# 11_-_AUDIO1.net
KiCad netlist of a schematic drawn in Altium Designer
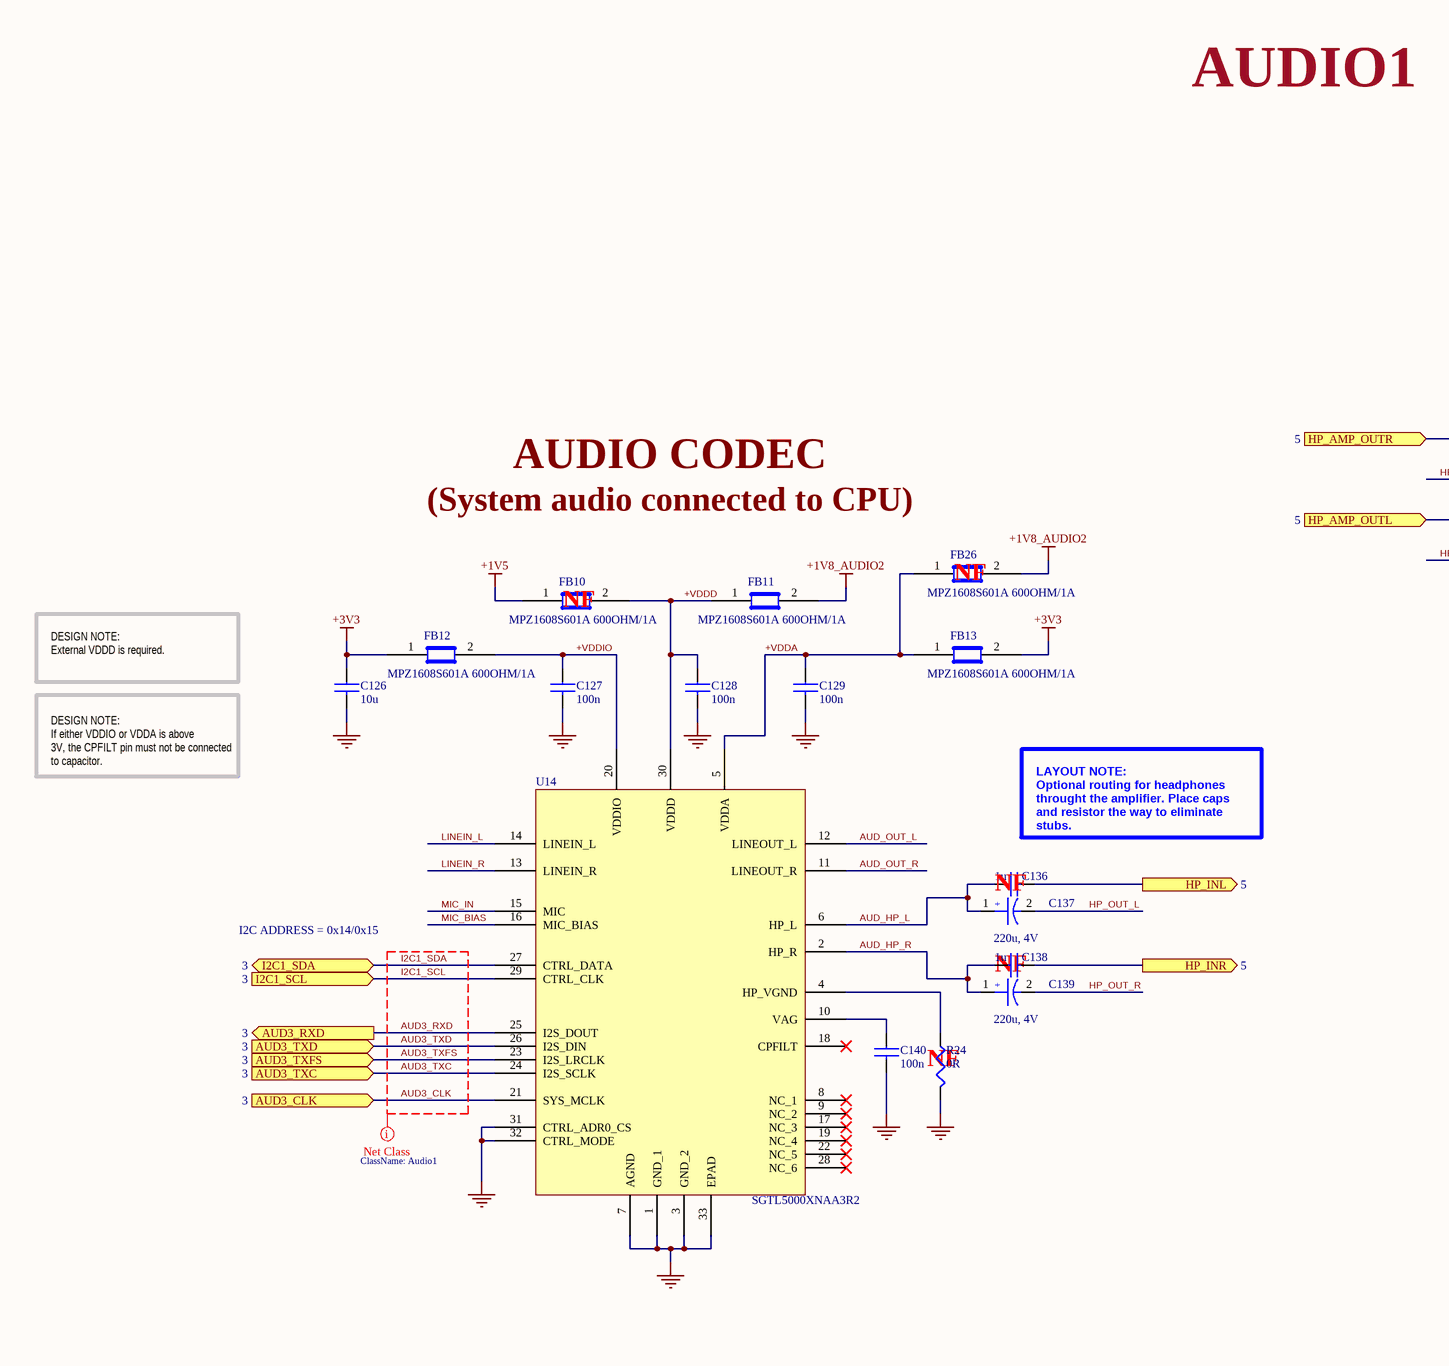
[diagram p0: [11] - AUDIO1.SchDoc, left]
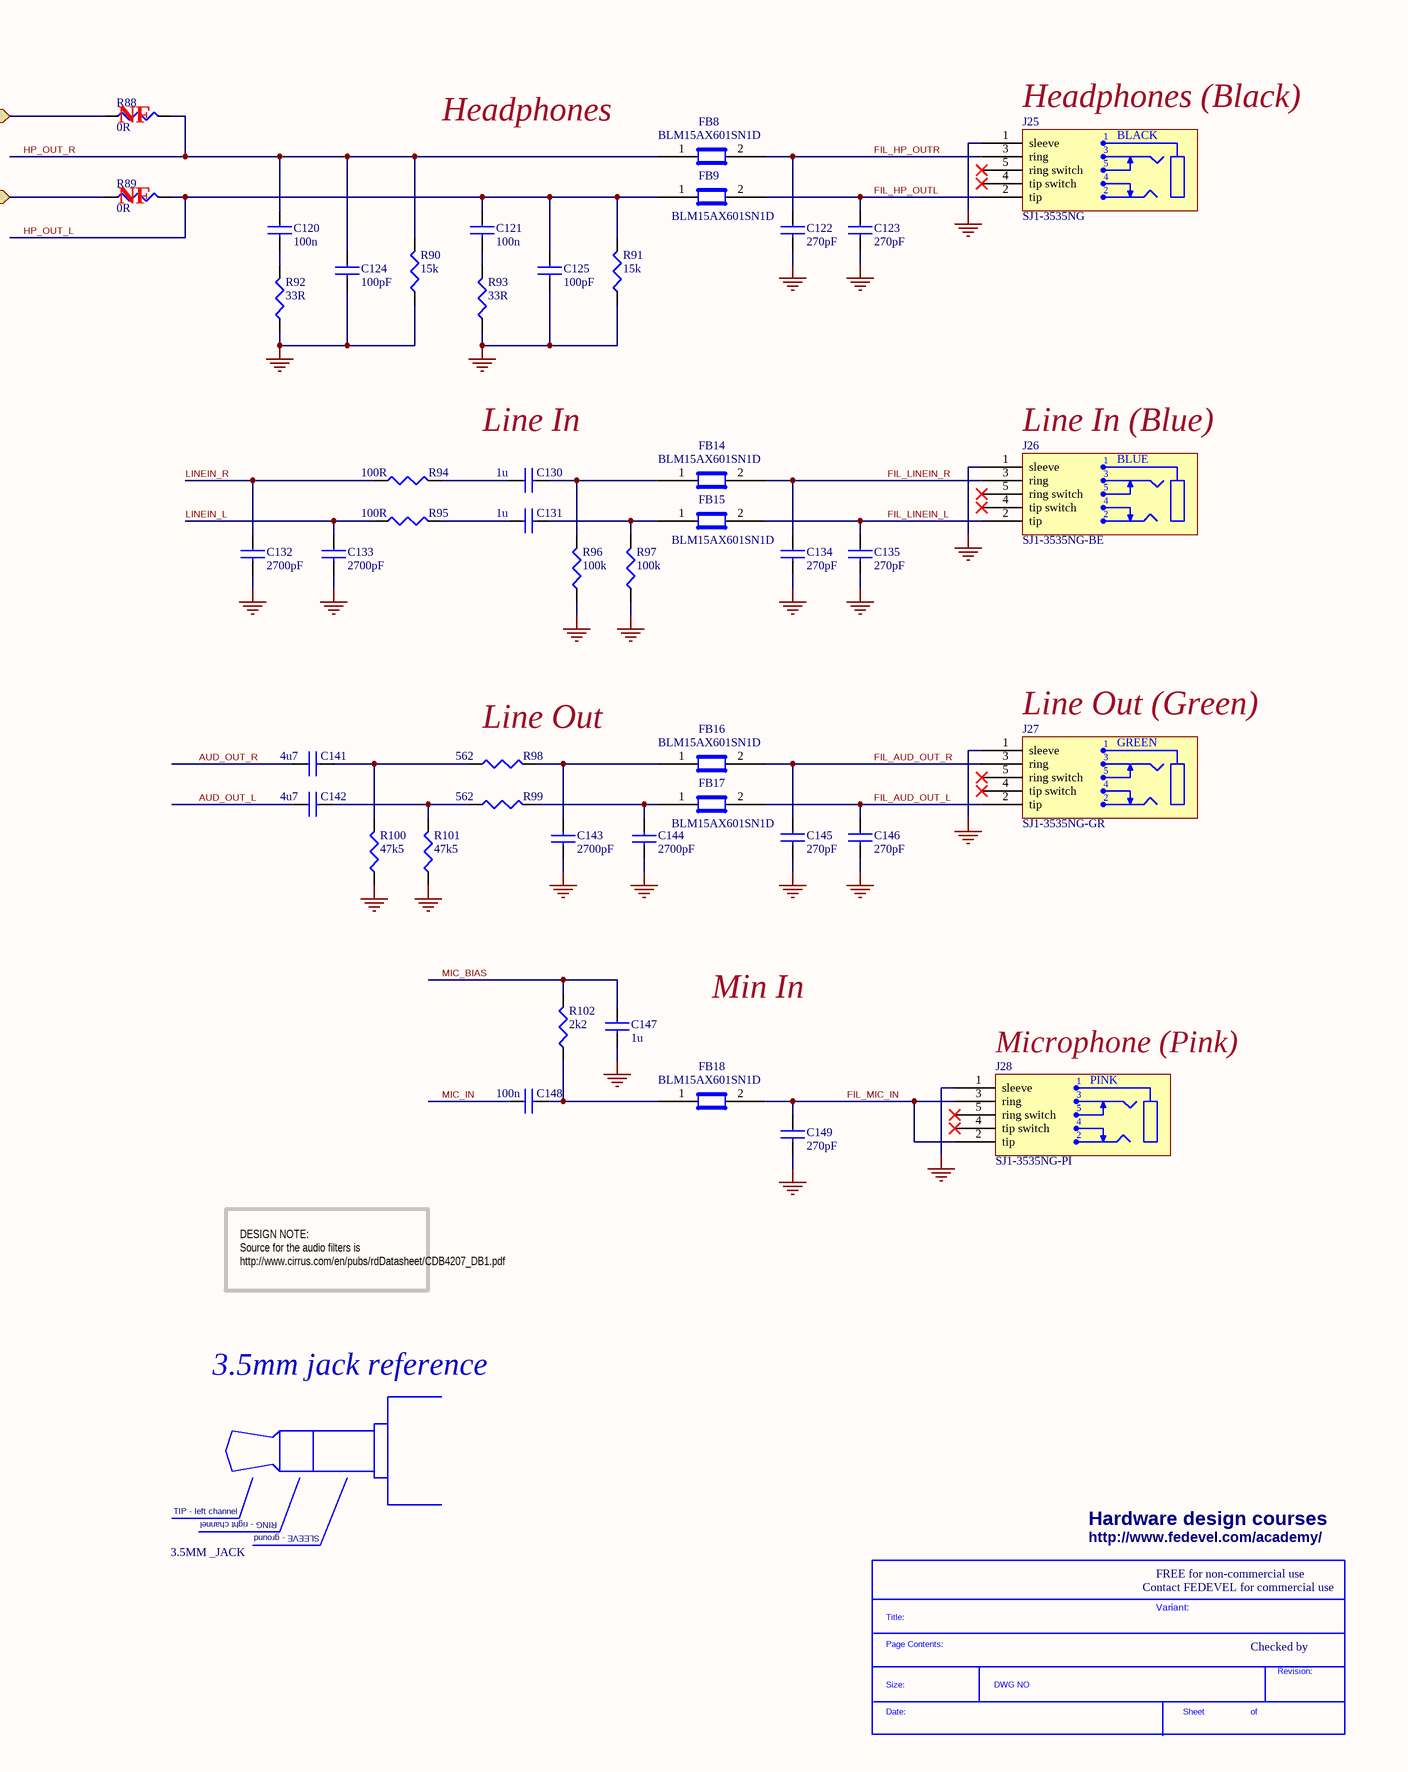
[diagram p1: [11] - AUDIO1.SchDoc, right]

(export (version "E")
  (design (tool "Eeschema 10.0.6"))
  (components
    (comp (ref "C120")
      (value "100n")
      (footprint "C0402")
      (description "CAP CER .10UF 50V X5R 10% 0402")
      (fields
        (field (name "MANUFACTURER") "TDK Corporation")
        (field (name "MANUFACTURER PART NUMBER") "C1005X5R1H104K")
      )
      (libsource (lib "Integrated_Library_RF_FEB_2012") (part "C1005X5R1H104K"))
    )
    (comp (ref "C121")
      (value "100n")
      (footprint "C0402")
      (description "CAP CER .10UF 50V X5R 10% 0402")
      (fields
        (field (name "MANUFACTURER") "TDK Corporation")
        (field (name "MANUFACTURER PART NUMBER") "C1005X5R1H104K")
      )
      (libsource (lib "Integrated_Library_RF_FEB_2012") (part "C1005X5R1H104K"))
    )
    (comp (ref "C122")
      (value "270pF")
      (footprint "C0402")
      (description "CAP CER 270PF 50V 10% X7R 0402")
      (fields
        (field (name "MANUFACTURER") "Murata Electronics North America")
        (field (name "MANUFACTURER PART NUMBER") "GRM155R71H271KA01D")
        (field (name ".CHECKED PCB") "RF")
        (field (name ".CHECKED SCH") "RF")
      )
      (libsource (lib "Integrated_Library_RF_FEB_2012") (part "GRM155R71H271KA01D"))
    )
    (comp (ref "C123")
      (value "270pF")
      (footprint "C0402")
      (description "CAP CER 270PF 50V 10% X7R 0402")
      (fields
        (field (name "MANUFACTURER") "Murata Electronics North America")
        (field (name "MANUFACTURER PART NUMBER") "GRM155R71H271KA01D")
        (field (name ".CHECKED PCB") "RF")
        (field (name ".CHECKED SCH") "RF")
      )
      (libsource (lib "Integrated_Library_RF_FEB_2012") (part "GRM155R71H271KA01D"))
    )
    (comp (ref "C124")
      (value "100pF")
      (footprint "C0402")
      (description "CAP CER 100PF 50V 5% NP0 0402")
      (fields
        (field (name "MANUFACTURER") "TDK Corporation")
        (field (name "MANUFACTURER PART NUMBER") "C1005C0G1H101J")
        (field (name ".CHECKED PCB") "RF")
        (field (name ".CHECKED SCH") "RF")
      )
      (libsource (lib "Integrated_Library_RF_FEB_2012") (part "C1005C0G1H101J"))
    )
    (comp (ref "C125")
      (value "100pF")
      (footprint "C0402")
      (description "CAP CER 100PF 50V 5% NP0 0402")
      (fields
        (field (name "MANUFACTURER") "TDK Corporation")
        (field (name "MANUFACTURER PART NUMBER") "C1005C0G1H101J")
        (field (name ".CHECKED PCB") "RF")
        (field (name ".CHECKED SCH") "RF")
      )
      (libsource (lib "Integrated_Library_RF_FEB_2012") (part "C1005C0G1H101J"))
    )
    (comp (ref "C126")
      (value "10u")
      (footprint "C0603")
      (description "CAP CER 10UF 6.3V X5R 20% 0603")
      (fields
        (field (name "MANUFACTURER") "TDK Corporation")
        (field (name "MANUFACTURER PART NUMBER") "C1608X5R0J106M")
      )
      (libsource (lib "Integrated_Library_RF_FEB_2012") (part "C1608X5R0J106M"))
    )
    (comp (ref "C127")
      (value "100n")
      (footprint "C0402")
      (description "CAP CER .10UF 50V X5R 10% 0402")
      (fields
        (field (name "MANUFACTURER") "TDK Corporation")
        (field (name "MANUFACTURER PART NUMBER") "C1005X5R1H104K")
      )
      (libsource (lib "Integrated_Library_RF_FEB_2012") (part "C1005X5R1H104K"))
    )
    (comp (ref "C128")
      (value "100n")
      (footprint "C0402")
      (description "CAP CER .10UF 50V X5R 10% 0402")
      (fields
        (field (name "MANUFACTURER") "TDK Corporation")
        (field (name "MANUFACTURER PART NUMBER") "C1005X5R1H104K")
      )
      (libsource (lib "Integrated_Library_RF_FEB_2012") (part "C1005X5R1H104K"))
    )
    (comp (ref "C129")
      (value "100n")
      (footprint "C0402")
      (description "CAP CER .10UF 50V X5R 10% 0402")
      (fields
        (field (name "MANUFACTURER") "TDK Corporation")
        (field (name "MANUFACTURER PART NUMBER") "C1005X5R1H104K")
      )
      (libsource (lib "Integrated_Library_RF_FEB_2012") (part "C1005X5R1H104K"))
    )
    (comp (ref "C130")
      (value "1u")
      (footprint "C0402")
      (description "CAP CER 1.0UF 16V X5R 0402")
      (fields
        (field (name "MANUFACTURER") "TDK Corporation")
        (field (name "MANUFACTURER PART NUMBER") "C1005X5R1C105K")
      )
      (libsource (lib "Integrated_Library_RF_FEB_2012") (part "C1005X5R1C105K"))
    )
    (comp (ref "C131")
      (value "1u")
      (footprint "C0402")
      (description "CAP CER 1.0UF 16V X5R 0402")
      (fields
        (field (name "MANUFACTURER") "TDK Corporation")
        (field (name "MANUFACTURER PART NUMBER") "C1005X5R1C105K")
      )
      (libsource (lib "Integrated_Library_RF_FEB_2012") (part "C1005X5R1C105K"))
    )
    (comp (ref "C132")
      (value "2700pF")
      (footprint "C0402")
      (description "CAP CER 2700PF 50V 10% X7R 0402")
      (fields
        (field (name "MANUFACTURER") "Murata Electronics North America")
        (field (name "MANUFACTURER PART NUMBER") "GRM155R71H272KA01D")
        (field (name ".CHECKED PCB") "RF")
        (field (name ".CHECKED SCH") "RF")
      )
      (libsource (lib "Integrated_Library_RF_FEB_2012") (part "GRM155R71H272KA01D"))
    )
    (comp (ref "C133")
      (value "2700pF")
      (footprint "C0402")
      (description "CAP CER 2700PF 50V 10% X7R 0402")
      (fields
        (field (name "MANUFACTURER") "Murata Electronics North America")
        (field (name "MANUFACTURER PART NUMBER") "GRM155R71H272KA01D")
        (field (name ".CHECKED PCB") "RF")
        (field (name ".CHECKED SCH") "RF")
      )
      (libsource (lib "Integrated_Library_RF_FEB_2012") (part "GRM155R71H272KA01D"))
    )
    (comp (ref "C134")
      (value "270pF")
      (footprint "C0402")
      (description "CAP CER 270PF 50V 10% X7R 0402")
      (fields
        (field (name "MANUFACTURER") "Murata Electronics North America")
        (field (name "MANUFACTURER PART NUMBER") "GRM155R71H271KA01D")
        (field (name ".CHECKED PCB") "RF")
        (field (name ".CHECKED SCH") "RF")
      )
      (libsource (lib "Integrated_Library_RF_FEB_2012") (part "GRM155R71H271KA01D"))
    )
    (comp (ref "C135")
      (value "270pF")
      (footprint "C0402")
      (description "CAP CER 270PF 50V 10% X7R 0402")
      (fields
        (field (name "MANUFACTURER") "Murata Electronics North America")
        (field (name "MANUFACTURER PART NUMBER") "GRM155R71H271KA01D")
        (field (name ".CHECKED PCB") "RF")
        (field (name ".CHECKED SCH") "RF")
      )
      (libsource (lib "Integrated_Library_RF_FEB_2012") (part "GRM155R71H271KA01D"))
    )
    (comp (ref "C136")
      (value "1u")
      (footprint "C0402")
      (description "CAP CER 1.0UF 16V X5R 0402")
      (fields
        (field (name "MANUFACTURER") "TDK Corporation")
        (field (name "MANUFACTURER PART NUMBER") "C1005X5R1C105K")
      )
      (libsource (lib "Integrated_Library_RF_FEB_2012") (part "C1005X5R1C105K"))
    )
    (comp (ref "C137")
      (value "220u, 4V")
      (footprint "C1206 -  TLN S Case Tantal")
      (description "CAP TANT 220UF 4V 20% 1206")
      (fields
        (field (name "MANUFACTURER") "AVX Corporation")
        (field (name "MANUFACTURER PART NUMBER") "TLNS227M004R3000")
        (field (name ".CHECKED PCB") "MM")
        (field (name ".CHECKED SCH") "MM")
      )
      (libsource (lib "Integrated_Library_RF_FEB_2012") (part "TLNS227M004R3000"))
    )
    (comp (ref "C138")
      (value "1u")
      (footprint "C0402")
      (description "CAP CER 1.0UF 16V X5R 0402")
      (fields
        (field (name "MANUFACTURER") "TDK Corporation")
        (field (name "MANUFACTURER PART NUMBER") "C1005X5R1C105K")
      )
      (libsource (lib "Integrated_Library_RF_FEB_2012") (part "C1005X5R1C105K"))
    )
    (comp (ref "C139")
      (value "220u, 4V")
      (footprint "C1206 -  TLN S Case Tantal")
      (description "CAP TANT 220UF 4V 20% 1206")
      (fields
        (field (name "MANUFACTURER") "AVX Corporation")
        (field (name "MANUFACTURER PART NUMBER") "TLNS227M004R3000")
        (field (name ".CHECKED PCB") "MM")
        (field (name ".CHECKED SCH") "MM")
      )
      (libsource (lib "Integrated_Library_RF_FEB_2012") (part "TLNS227M004R3000"))
    )
    (comp (ref "C140")
      (value "100n")
      (footprint "C0402")
      (description "CAP CER .10UF 50V X5R 10% 0402")
      (fields
        (field (name "MANUFACTURER") "TDK Corporation")
        (field (name "MANUFACTURER PART NUMBER") "C1005X5R1H104K")
      )
      (libsource (lib "Integrated_Library_RF_FEB_2012") (part "C1005X5R1H104K"))
    )
    (comp (ref "C141")
      (value "4u7")
      (footprint "C0402")
      (description "CAP CER 4.7UF 10V 20% X5R 0402")
      (fields
        (field (name "MANUFACTURER") "TDK Corporation")
        (field (name "MANUFACTURER PART NUMBER") "C1005X5R1A475M")
        (field (name ".CHECKED PCB") "RF")
        (field (name ".CHECKED SCH") "RF")
      )
      (libsource (lib "Integrated_Library_RF_FEB_2012") (part "C1005X5R1A475M"))
    )
    (comp (ref "C142")
      (value "4u7")
      (footprint "C0402")
      (description "CAP CER 4.7UF 10V 20% X5R 0402")
      (fields
        (field (name "MANUFACTURER") "TDK Corporation")
        (field (name "MANUFACTURER PART NUMBER") "C1005X5R1A475M")
        (field (name ".CHECKED PCB") "RF")
        (field (name ".CHECKED SCH") "RF")
      )
      (libsource (lib "Integrated_Library_RF_FEB_2012") (part "C1005X5R1A475M"))
    )
    (comp (ref "C143")
      (value "2700pF")
      (footprint "C0402")
      (description "CAP CER 2700PF 50V 10% X7R 0402")
      (fields
        (field (name "MANUFACTURER") "Murata Electronics North America")
        (field (name "MANUFACTURER PART NUMBER") "GRM155R71H272KA01D")
        (field (name ".CHECKED PCB") "RF")
        (field (name ".CHECKED SCH") "RF")
      )
      (libsource (lib "Integrated_Library_RF_FEB_2012") (part "GRM155R71H272KA01D"))
    )
    (comp (ref "C144")
      (value "2700pF")
      (footprint "C0402")
      (description "CAP CER 2700PF 50V 10% X7R 0402")
      (fields
        (field (name "MANUFACTURER") "Murata Electronics North America")
        (field (name "MANUFACTURER PART NUMBER") "GRM155R71H272KA01D")
        (field (name ".CHECKED PCB") "RF")
        (field (name ".CHECKED SCH") "RF")
      )
      (libsource (lib "Integrated_Library_RF_FEB_2012") (part "GRM155R71H272KA01D"))
    )
    (comp (ref "C145")
      (value "270pF")
      (footprint "C0402")
      (description "CAP CER 270PF 50V 10% X7R 0402")
      (fields
        (field (name "MANUFACTURER") "Murata Electronics North America")
        (field (name "MANUFACTURER PART NUMBER") "GRM155R71H271KA01D")
        (field (name ".CHECKED PCB") "RF")
        (field (name ".CHECKED SCH") "RF")
      )
      (libsource (lib "Integrated_Library_RF_FEB_2012") (part "GRM155R71H271KA01D"))
    )
    (comp (ref "C146")
      (value "270pF")
      (footprint "C0402")
      (description "CAP CER 270PF 50V 10% X7R 0402")
      (fields
        (field (name "MANUFACTURER") "Murata Electronics North America")
        (field (name "MANUFACTURER PART NUMBER") "GRM155R71H271KA01D")
        (field (name ".CHECKED PCB") "RF")
        (field (name ".CHECKED SCH") "RF")
      )
      (libsource (lib "Integrated_Library_RF_FEB_2012") (part "GRM155R71H271KA01D"))
    )
    (comp (ref "C147")
      (value "1u")
      (footprint "C0402")
      (description "CAP CER 1.0UF 16V X5R 0402")
      (fields
        (field (name "MANUFACTURER") "TDK Corporation")
        (field (name "MANUFACTURER PART NUMBER") "C1005X5R1C105K")
      )
      (libsource (lib "Integrated_Library_RF_FEB_2012") (part "C1005X5R1C105K"))
    )
    (comp (ref "C148")
      (value "100n")
      (footprint "C0402")
      (description "CAP CER .10UF 50V X5R 10% 0402")
      (fields
        (field (name "MANUFACTURER") "TDK Corporation")
        (field (name "MANUFACTURER PART NUMBER") "C1005X5R1H104K")
      )
      (libsource (lib "Integrated_Library_RF_FEB_2012") (part "C1005X5R1H104K"))
    )
    (comp (ref "C149")
      (value "270pF")
      (footprint "C0402")
      (description "CAP CER 270PF 50V 10% X7R 0402")
      (fields
        (field (name "MANUFACTURER") "Murata Electronics North America")
        (field (name "MANUFACTURER PART NUMBER") "GRM155R71H271KA01D")
        (field (name ".CHECKED PCB") "RF")
        (field (name ".CHECKED SCH") "RF")
      )
      (libsource (lib "Integrated_Library_RF_FEB_2012") (part "GRM155R71H271KA01D"))
    )
    (comp (ref "FB8")
      (value "BLM15AX601SN1D")
      (footprint "C0402")
      (description "FERRITE CHIP 600 OHM 0402")
      (fields (field (name "MANUFACTURER") "Murata Electronics North America"))
      (libsource (lib "Integrated_Library_RF_FEB_2012") (part "BLM15AX601SN1D"))
    )
    (comp (ref "FB9")
      (value "BLM15AX601SN1D")
      (footprint "C0402")
      (description "FERRITE CHIP 600 OHM 0402")
      (fields (field (name "MANUFACTURER") "Murata Electronics North America"))
      (libsource (lib "Integrated_Library_RF_FEB_2012") (part "BLM15AX601SN1D"))
    )
    (comp (ref "FB10")
      (value "MPZ1608S601A 600OHM/1A")
      (footprint "C0603")
      (description "FERRITE CHIP BEAD 600 OHM SMD 1A")
      (fields
        (field (name "MANUFACTURER") "TDK Corporation")
        (field (name "MANUFACTURER PART NUMBER") "MPZ1608S601A")
        (field (name ".CHECKED PCB") "RF")
        (field (name ".CHECKED SCH") "RF")
      )
      (libsource (lib "Integrated_Library_RF_FEB_2012") (part "MPZ1608S601A"))
    )
    (comp (ref "FB11")
      (value "MPZ1608S601A 600OHM/1A")
      (footprint "C0603")
      (description "FERRITE CHIP BEAD 600 OHM SMD 1A")
      (fields
        (field (name "MANUFACTURER") "TDK Corporation")
        (field (name "MANUFACTURER PART NUMBER") "MPZ1608S601A")
        (field (name ".CHECKED PCB") "RF")
        (field (name ".CHECKED SCH") "RF")
      )
      (libsource (lib "Integrated_Library_RF_FEB_2012") (part "MPZ1608S601A"))
    )
    (comp (ref "FB12")
      (value "MPZ1608S601A 600OHM/1A")
      (footprint "C0603")
      (description "FERRITE CHIP BEAD 600 OHM SMD 1A")
      (fields
        (field (name "MANUFACTURER") "TDK Corporation")
        (field (name "MANUFACTURER PART NUMBER") "MPZ1608S601A")
        (field (name ".CHECKED PCB") "RF")
        (field (name ".CHECKED SCH") "RF")
      )
      (libsource (lib "Integrated_Library_RF_FEB_2012") (part "MPZ1608S601A"))
    )
    (comp (ref "FB13")
      (value "MPZ1608S601A 600OHM/1A")
      (footprint "C0603")
      (description "FERRITE CHIP BEAD 600 OHM SMD 1A")
      (fields
        (field (name "MANUFACTURER") "TDK Corporation")
        (field (name "MANUFACTURER PART NUMBER") "MPZ1608S601A")
        (field (name ".CHECKED PCB") "RF")
        (field (name ".CHECKED SCH") "RF")
      )
      (libsource (lib "Integrated_Library_RF_FEB_2012") (part "MPZ1608S601A"))
    )
    (comp (ref "FB14")
      (value "BLM15AX601SN1D")
      (footprint "C0402")
      (description "FERRITE CHIP 600 OHM 0402")
      (fields (field (name "MANUFACTURER") "Murata Electronics North America"))
      (libsource (lib "Integrated_Library_RF_FEB_2012") (part "BLM15AX601SN1D"))
    )
    (comp (ref "FB15")
      (value "BLM15AX601SN1D")
      (footprint "C0402")
      (description "FERRITE CHIP 600 OHM 0402")
      (fields (field (name "MANUFACTURER") "Murata Electronics North America"))
      (libsource (lib "Integrated_Library_RF_FEB_2012") (part "BLM15AX601SN1D"))
    )
    (comp (ref "FB16")
      (value "BLM15AX601SN1D")
      (footprint "C0402")
      (description "FERRITE CHIP 600 OHM 0402")
      (fields (field (name "MANUFACTURER") "Murata Electronics North America"))
      (libsource (lib "Integrated_Library_RF_FEB_2012") (part "BLM15AX601SN1D"))
    )
    (comp (ref "FB17")
      (value "BLM15AX601SN1D")
      (footprint "C0402")
      (description "FERRITE CHIP 600 OHM 0402")
      (fields (field (name "MANUFACTURER") "Murata Electronics North America"))
      (libsource (lib "Integrated_Library_RF_FEB_2012") (part "BLM15AX601SN1D"))
    )
    (comp (ref "FB18")
      (value "BLM15AX601SN1D")
      (footprint "C0402")
      (description "FERRITE CHIP 600 OHM 0402")
      (fields (field (name "MANUFACTURER") "Murata Electronics North America"))
      (libsource (lib "Integrated_Library_RF_FEB_2012") (part "BLM15AX601SN1D"))
    )
    (comp (ref "FB26")
      (value "MPZ1608S601A 600OHM/1A")
      (footprint "C0603")
      (description "FERRITE CHIP BEAD 600 OHM SMD 1A")
      (fields
        (field (name "MANUFACTURER") "TDK Corporation")
        (field (name "MANUFACTURER PART NUMBER") "MPZ1608S601A")
        (field (name ".CHECKED PCB") "RF")
        (field (name ".CHECKED SCH") "RF")
      )
      (libsource (lib "Integrated_Library_RF_FEB_2012") (part "MPZ1608S601A"))
    )
    (comp (ref "J25")
      (value "SJ1-3535NG")
      (footprint "SJ1-3535NG")
      (description "CONN JACK STEREO R/A 5PIN 3.5MM")
      (fields
        (field (name "MANUFACTURER") "CUI Inc")
        (field (name ".CHECKED PCB") "RF")
        (field (name ".CHECKED SCH") "RF")
      )
      (libsource (lib "Integrated_Library_RF_FEB_2012") (part "SJ1-3535NG"))
    )
    (comp (ref "J26")
      (value "SJ1-3535NG-BE")
      (footprint "SJ1-3535NG")
      (description "CONN JACK STEREO 5POS 3.5MM PCB")
      (fields
        (field (name "MANUFACTURER") "CUI Inc")
        (field (name ".CHECKED PCB") "RF")
        (field (name ".CHECKED SCH") "RF")
      )
      (libsource (lib "Integrated_Library_RF_FEB_2012") (part "SJ1-3535NG-BE"))
    )
    (comp (ref "J27")
      (value "SJ1-3535NG-GR")
      (footprint "SJ1-3535NG")
      (description "CONN JACK STEREO 5POS 3.5MM PCB")
      (fields
        (field (name "MANUFACTURER") "CUI Inc")
        (field (name ".CHECKED PCB") "RF")
        (field (name ".CHECKED SCH") "RF")
      )
      (libsource (lib "Integrated_Library_RF_FEB_2012") (part "SJ1-3535NG-GR"))
    )
    (comp (ref "J28")
      (value "SJ1-3535NG-PI")
      (footprint "SJ1-3535NG")
      (description "CONN JACK STEREO 5POS 3.5MM PCB")
      (fields
        (field (name "MANUFACTURER") "CUI Inc")
        (field (name ".CHECKED PCB") "RF")
        (field (name ".CHECKED SCH") "RF")
      )
      (libsource (lib "Integrated_Library_RF_FEB_2012") (part "SJ1-3535NG-PI"))
    )
    (comp (ref "R24")
      (value "0R")
      (footprint "R0402")
      (description "RES 0.0 OHM 1/16W 0402 SMD")
      (fields
        (field (name "MANUFACTURER") "Yageo")
        (field (name "MANUFACTURER PART NUMBER") "RC0402JR-070RL")
      )
      (libsource (lib "Integrated_Library_RF_FEB_2012") (part "RC0402JR-070RL"))
    )
    (comp (ref "R88")
      (value "0R")
      (footprint "R0402")
      (description "RES 0.0 OHM 1/16W 0402 SMD")
      (fields
        (field (name "MANUFACTURER") "Yageo")
        (field (name "MANUFACTURER PART NUMBER") "RC0402JR-070RL")
      )
      (libsource (lib "Integrated_Library_RF_FEB_2012") (part "RC0402JR-070RL"))
    )
    (comp (ref "R89")
      (value "0R")
      (footprint "R0402")
      (description "RES 0.0 OHM 1/16W 0402 SMD")
      (fields
        (field (name "MANUFACTURER") "Yageo")
        (field (name "MANUFACTURER PART NUMBER") "RC0402JR-070RL")
      )
      (libsource (lib "Integrated_Library_RF_FEB_2012") (part "RC0402JR-070RL"))
    )
    (comp (ref "R90")
      (value "15k")
      (footprint "R0402")
      (description "RES 15.0K OHM 1/16W 1% 0402 SMD")
      (fields
        (field (name "MANUFACTURER") "Yageo")
        (field (name "MANUFACTURER PART NUMBER") "RC0402FR-0715KL")
      )
      (libsource (lib "Integrated_Library_RF_FEB_2012") (part "RC0402FR-0715KL"))
    )
    (comp (ref "R91")
      (value "15k")
      (footprint "R0402")
      (description "RES 15.0K OHM 1/16W 1% 0402 SMD")
      (fields
        (field (name "MANUFACTURER") "Yageo")
        (field (name "MANUFACTURER PART NUMBER") "RC0402FR-0715KL")
      )
      (libsource (lib "Integrated_Library_RF_FEB_2012") (part "RC0402FR-0715KL"))
    )
    (comp (ref "R92")
      (value "33R")
      (footprint "R0402")
      (description "RES TF 33 OHM 1% 1/16W 0402")
      (fields
        (field (name "MANUFACTURER") "Stackpole Electronics Inc")
        (field (name "MANUFACTURER PART NUMBER") "RMCF0402FT33R0")
        (field (name ".CHECKED PCB") "RF")
        (field (name ".CHECKED SCH") "RF")
      )
      (libsource (lib "Integrated_Library_RF_FEB_2012") (part "RMCF0402FT33R0"))
    )
    (comp (ref "R93")
      (value "33R")
      (footprint "R0402")
      (description "RES TF 33 OHM 1% 1/16W 0402")
      (fields
        (field (name "MANUFACTURER") "Stackpole Electronics Inc")
        (field (name "MANUFACTURER PART NUMBER") "RMCF0402FT33R0")
        (field (name ".CHECKED PCB") "RF")
        (field (name ".CHECKED SCH") "RF")
      )
      (libsource (lib "Integrated_Library_RF_FEB_2012") (part "RMCF0402FT33R0"))
    )
    (comp (ref "R94")
      (value "100R")
      (footprint "R0402")
      (description "RES 100 OHM 1/16W 1% 0402 SMD")
      (fields
        (field (name "MANUFACTURER") "Yageo")
        (field (name "MANUFACTURER PART NUMBER") "RC0402FR-07100RL")
        (field (name ".CHECKED PCB") "RF")
        (field (name ".CHECKED SCH") "RF")
      )
      (libsource (lib "Integrated_Library_RF_FEB_2012") (part "RC0402FR-07100RL"))
    )
    (comp (ref "R95")
      (value "100R")
      (footprint "R0402")
      (description "RES 100 OHM 1/16W 1% 0402 SMD")
      (fields
        (field (name "MANUFACTURER") "Yageo")
        (field (name "MANUFACTURER PART NUMBER") "RC0402FR-07100RL")
        (field (name ".CHECKED PCB") "RF")
        (field (name ".CHECKED SCH") "RF")
      )
      (libsource (lib "Integrated_Library_RF_FEB_2012") (part "RC0402FR-07100RL"))
    )
    (comp (ref "R96")
      (value "100k")
      (footprint "R0402")
      (description "RES 100K OHM 1/16W 1% 0402 SMD")
      (fields
        (field (name "MANUFACTURER") "Stackpole Electronics Inc")
        (field (name "MANUFACTURER PART NUMBER") "RMCF0402FT100K")
      )
      (libsource (lib "Integrated_Library_RF_FEB_2012") (part "RMCF0402FT100K"))
    )
    (comp (ref "R97")
      (value "100k")
      (footprint "R0402")
      (description "RES 100K OHM 1/16W 1% 0402 SMD")
      (fields
        (field (name "MANUFACTURER") "Stackpole Electronics Inc")
        (field (name "MANUFACTURER PART NUMBER") "RMCF0402FT100K")
      )
      (libsource (lib "Integrated_Library_RF_FEB_2012") (part "RMCF0402FT100K"))
    )
    (comp (ref "R98")
      (value "562")
      (footprint "R0402")
      (description "RES 562 OHM 1/16W 1% 0402 SMD")
      (fields
        (field (name "MANUFACTURER") "Vishay Dale")
        (field (name "MANUFACTURER PART NUMBER") "CRCW0402562RFKED")
        (field (name ".CHECKED PCB") "RF")
        (field (name ".CHECKED SCH") "RF")
      )
      (libsource (lib "Integrated_Library_RF_FEB_2012") (part "CRCW0402562RFKED"))
    )
    (comp (ref "R99")
      (value "562")
      (footprint "R0402")
      (description "RES 562 OHM 1/16W 1% 0402 SMD")
      (fields
        (field (name "MANUFACTURER") "Vishay Dale")
        (field (name "MANUFACTURER PART NUMBER") "CRCW0402562RFKED")
        (field (name ".CHECKED PCB") "RF")
        (field (name ".CHECKED SCH") "RF")
      )
      (libsource (lib "Integrated_Library_RF_FEB_2012") (part "CRCW0402562RFKED"))
    )
    (comp (ref "R100")
      (value "47k5")
      (footprint "R0402")
      (description "RES 47.5K OHM 1/16W 1% 0402 SMD")
      (fields
        (field (name "MANUFACTURER") "Yageo")
        (field (name "MANUFACTURER PART NUMBER") "RC0402FR-0747K5L")
        (field (name ".CHECKED PCB") "RF")
        (field (name ".CHECKED SCH") "RF")
      )
      (libsource (lib "Integrated_Library_RF_FEB_2012") (part "RC0402FR-0747K5L"))
    )
    (comp (ref "R101")
      (value "47k5")
      (footprint "R0402")
      (description "RES 47.5K OHM 1/16W 1% 0402 SMD")
      (fields
        (field (name "MANUFACTURER") "Yageo")
        (field (name "MANUFACTURER PART NUMBER") "RC0402FR-0747K5L")
        (field (name ".CHECKED PCB") "RF")
        (field (name ".CHECKED SCH") "RF")
      )
      (libsource (lib "Integrated_Library_RF_FEB_2012") (part "RC0402FR-0747K5L"))
    )
    (comp (ref "R102")
      (value "2k2")
      (footprint "R0402")
      (description "RES 2.20K OHM 1/16W 1% 0402 SMD")
      (fields
        (field (name "MANUFACTURER") "Yageo")
        (field (name "MANUFACTURER PART NUMBER") "RC0402FR-072K2L")
      )
      (libsource (lib "Integrated_Library_RF_FEB_2012") (part "RC0402FR-072K2L"))
    )
    (comp (ref "U14")
      (value "SGTL5000XNAA3R2")
      (footprint "QFN32 5x5x0.85")
      (description "IC AUDIO CODEC STEREO 32-QFN")
      (fields
        (field (name "MANUFACTURER") "Freescale Semiconductor")
        (field (name ".CREATOR") "MM")
        (field (name ".CHECKED PCB") "RF, used by MM")
        (field (name ".CHECKED SCH") "MM")
      )
      (libsource (lib "Integrated_Library_RF_FEB_2012") (part "SGTL5000XNAA3R2"))
    )
  )
  (nets
    (net (code "1") (name "+1V5") (class "Default")
      (node (ref "FB10") (pin "1") (pinfunction "1_1") (pintype "passive"))
    )
    (net (code "2") (name "+1V8_AUDIO2") (class "Default")
      (node (ref "FB11") (pin "2") (pinfunction "2_2") (pintype "passive"))
      (node (ref "FB26") (pin "2") (pinfunction "2_2") (pintype "passive"))
    )
    (net (code "3") (name "+3V3") (class "Default")
      (node (ref "C126") (pin "1") (pinfunction "1_1") (pintype "passive"))
      (node (ref "FB12") (pin "1") (pinfunction "1_1") (pintype "passive"))
      (node (ref "FB13") (pin "2") (pinfunction "2_2") (pintype "passive"))
    )
    (net (code "4") (name "/+VDDA") (class "Default")
      (node (ref "C129") (pin "1") (pinfunction "1_1") (pintype "passive"))
      (node (ref "FB13") (pin "1") (pinfunction "1_1") (pintype "passive"))
      (node (ref "FB26") (pin "1") (pinfunction "1_1") (pintype "passive"))
      (node (ref "U14") (pin "5") (pinfunction "VDDA_5") (pintype "passive"))
    )
    (net (code "5") (name "/+VDDD") (class "Default")
      (node (ref "C128") (pin "1") (pinfunction "1_1") (pintype "passive"))
      (node (ref "FB10") (pin "2") (pinfunction "2_2") (pintype "passive"))
      (node (ref "FB11") (pin "1") (pinfunction "1_1") (pintype "passive"))
      (node (ref "U14") (pin "30") (pinfunction "VDDD_30") (pintype "passive"))
    )
    (net (code "6") (name "/+VDDIO") (class "Default")
      (node (ref "C127") (pin "1") (pinfunction "1_1") (pintype "passive"))
      (node (ref "FB12") (pin "2") (pinfunction "2_2") (pintype "passive"))
      (node (ref "U14") (pin "20") (pinfunction "VDDIO_20") (pintype "passive"))
    )
    (net (code "7") (name "/AUD3_CLK") (class "Default")
      (node (ref "U14") (pin "21") (pinfunction "SYS_MCLK_21") (pintype "passive"))
    )
    (net (code "8") (name "/AUD3_RXD") (class "Default")
      (node (ref "U14") (pin "25") (pinfunction "I2S_DOUT_25") (pintype "passive"))
    )
    (net (code "9") (name "/AUD3_TXC") (class "Default")
      (node (ref "U14") (pin "24") (pinfunction "I2S_SCLK_24") (pintype "passive"))
    )
    (net (code "10") (name "/AUD3_TXD") (class "Default")
      (node (ref "U14") (pin "26") (pinfunction "I2S_DIN_26") (pintype "passive"))
    )
    (net (code "11") (name "/AUD3_TXFS") (class "Default")
      (node (ref "U14") (pin "23") (pinfunction "I2S_LRCLK_23") (pintype "passive"))
    )
    (net (code "12") (name "/AUD_HP_L") (class "Default")
      (node (ref "C136") (pin "1") (pinfunction "1_1") (pintype "passive"))
      (node (ref "C137") (pin "1") (pinfunction "1_1") (pintype "passive"))
      (node (ref "U14") (pin "6") (pinfunction "HP_L_6") (pintype "passive"))
    )
    (net (code "13") (name "/AUD_HP_R") (class "Default")
      (node (ref "C138") (pin "1") (pinfunction "1_1") (pintype "passive"))
      (node (ref "C139") (pin "1") (pinfunction "1_1") (pintype "passive"))
      (node (ref "U14") (pin "2") (pinfunction "HP_R_2") (pintype "passive"))
    )
    (net (code "14") (name "/AUD_OUT_L") (class "Default")
      (node (ref "C142") (pin "1") (pinfunction "1_1") (pintype "passive"))
      (node (ref "U14") (pin "12") (pinfunction "LINEOUT_L_12") (pintype "passive"))
    )
    (net (code "15") (name "/AUD_OUT_R") (class "Default")
      (node (ref "C141") (pin "1") (pinfunction "1_1") (pintype "passive"))
      (node (ref "U14") (pin "11") (pinfunction "LINEOUT_R_11") (pintype "passive"))
    )
    (net (code "16") (name "/FIL_AUD_OUT_L") (class "Default")
      (node (ref "C146") (pin "1") (pinfunction "1_1") (pintype "passive"))
      (node (ref "FB17") (pin "2") (pinfunction "2_2") (pintype "passive"))
      (node (ref "J27") (pin "2") (pinfunction "tip_2") (pintype "passive"))
    )
    (net (code "17") (name "/FIL_AUD_OUT_R") (class "Default")
      (node (ref "C145") (pin "1") (pinfunction "1_1") (pintype "passive"))
      (node (ref "FB16") (pin "2") (pinfunction "2_2") (pintype "passive"))
      (node (ref "J27") (pin "3") (pinfunction "ring_3") (pintype "passive"))
    )
    (net (code "18") (name "/FIL_HP_OUTL") (class "Default")
      (node (ref "C123") (pin "1") (pinfunction "1_1") (pintype "passive"))
      (node (ref "FB9") (pin "2") (pinfunction "2_2") (pintype "passive"))
      (node (ref "J25") (pin "2") (pinfunction "tip_2") (pintype "passive"))
    )
    (net (code "19") (name "/FIL_HP_OUTR") (class "Default")
      (node (ref "C122") (pin "1") (pinfunction "1_1") (pintype "passive"))
      (node (ref "FB8") (pin "2") (pinfunction "2_2") (pintype "passive"))
      (node (ref "J25") (pin "3") (pinfunction "ring_3") (pintype "passive"))
    )
    (net (code "20") (name "/FIL_LINEIN_L") (class "Default")
      (node (ref "C135") (pin "1") (pinfunction "1_1") (pintype "passive"))
      (node (ref "FB15") (pin "2") (pinfunction "2_2") (pintype "passive"))
      (node (ref "J26") (pin "2") (pinfunction "tip_2") (pintype "passive"))
    )
    (net (code "21") (name "/FIL_LINEIN_R") (class "Default")
      (node (ref "C134") (pin "1") (pinfunction "1_1") (pintype "passive"))
      (node (ref "FB14") (pin "2") (pinfunction "2_2") (pintype "passive"))
      (node (ref "J26") (pin "3") (pinfunction "ring_3") (pintype "passive"))
    )
    (net (code "22") (name "/FIL_MIC_IN") (class "Default")
      (node (ref "C149") (pin "1") (pinfunction "1_1") (pintype "passive"))
      (node (ref "FB18") (pin "2") (pinfunction "2_2") (pintype "passive"))
      (node (ref "J28") (pin "2") (pinfunction "tip_2") (pintype "passive"))
      (node (ref "J28") (pin "3") (pinfunction "ring_3") (pintype "passive"))
    )
    (net (code "23") (name "/HP_AMP_OUTL") (class "Default")
      (node (ref "R89") (pin "1") (pinfunction "1_1") (pintype "passive"))
    )
    (net (code "24") (name "/HP_AMP_OUTR") (class "Default")
      (node (ref "R88") (pin "1") (pinfunction "1_1") (pintype "passive"))
    )
    (net (code "25") (name "/HP_INL") (class "Default")
      (node (ref "C136") (pin "2") (pinfunction "2_2") (pintype "passive"))
    )
    (net (code "26") (name "/HP_INR") (class "Default")
      (node (ref "C138") (pin "2") (pinfunction "2_2") (pintype "passive"))
    )
    (net (code "27") (name "/HP_OUT_L") (class "Default")
      (node (ref "C121") (pin "1") (pinfunction "1_1") (pintype "passive"))
      (node (ref "C125") (pin "1") (pinfunction "1_1") (pintype "passive"))
      (node (ref "C137") (pin "2") (pinfunction "2_2") (pintype "passive"))
      (node (ref "FB9") (pin "1") (pinfunction "1_1") (pintype "passive"))
      (node (ref "R89") (pin "2") (pinfunction "2_2") (pintype "passive"))
      (node (ref "R91") (pin "2") (pinfunction "2_2") (pintype "passive"))
    )
    (net (code "28") (name "/HP_OUT_R") (class "Default")
      (node (ref "C120") (pin "1") (pinfunction "1_1") (pintype "passive"))
      (node (ref "C124") (pin "1") (pinfunction "1_1") (pintype "passive"))
      (node (ref "C139") (pin "2") (pinfunction "2_2") (pintype "passive"))
      (node (ref "FB8") (pin "1") (pinfunction "1_1") (pintype "passive"))
      (node (ref "R88") (pin "2") (pinfunction "2_2") (pintype "passive"))
      (node (ref "R90") (pin "2") (pinfunction "2_2") (pintype "passive"))
    )
    (net (code "29") (name "/I2C1_SCL") (class "Default")
      (node (ref "U14") (pin "29") (pinfunction "CTRL_CLK_29") (pintype "passive"))
    )
    (net (code "30") (name "/I2C1_SDA") (class "Default")
      (node (ref "U14") (pin "27") (pinfunction "CTRL_DATA_27") (pintype "passive"))
    )
    (net (code "31") (name "/LINEIN_L") (class "Default")
      (node (ref "C133") (pin "1") (pinfunction "1_1") (pintype "passive"))
      (node (ref "R95") (pin "1") (pinfunction "1_1") (pintype "passive"))
      (node (ref "U14") (pin "14") (pinfunction "LINEIN_L_14") (pintype "passive"))
    )
    (net (code "32") (name "/LINEIN_R") (class "Default")
      (node (ref "C132") (pin "1") (pinfunction "1_1") (pintype "passive"))
      (node (ref "R94") (pin "1") (pinfunction "1_1") (pintype "passive"))
      (node (ref "U14") (pin "13") (pinfunction "LINEIN_R_13") (pintype "passive"))
    )
    (net (code "33") (name "/MIC_BIAS") (class "Default")
      (node (ref "C147") (pin "1") (pinfunction "1_1") (pintype "passive"))
      (node (ref "R102") (pin "2") (pinfunction "2_2") (pintype "passive"))
      (node (ref "U14") (pin "16") (pinfunction "MIC_BIAS_16") (pintype "passive"))
    )
    (net (code "34") (name "/MIC_IN") (class "Default")
      (node (ref "C148") (pin "1") (pinfunction "1_1") (pintype "passive"))
      (node (ref "U14") (pin "15") (pinfunction "MIC_15") (pintype "passive"))
    )
    (net (code "35") (name "GND") (class "Default")
      (node (ref "C122") (pin "2") (pinfunction "2_2") (pintype "passive"))
      (node (ref "C123") (pin "2") (pinfunction "2_2") (pintype "passive"))
      (node (ref "C124") (pin "2") (pinfunction "2_2") (pintype "passive"))
      (node (ref "C125") (pin "2") (pinfunction "2_2") (pintype "passive"))
      (node (ref "C126") (pin "2") (pinfunction "2_2") (pintype "passive"))
      (node (ref "C127") (pin "2") (pinfunction "2_2") (pintype "passive"))
      (node (ref "C128") (pin "2") (pinfunction "2_2") (pintype "passive"))
      (node (ref "C129") (pin "2") (pinfunction "2_2") (pintype "passive"))
      (node (ref "C132") (pin "2") (pinfunction "2_2") (pintype "passive"))
      (node (ref "C133") (pin "2") (pinfunction "2_2") (pintype "passive"))
      (node (ref "C134") (pin "2") (pinfunction "2_2") (pintype "passive"))
      (node (ref "C135") (pin "2") (pinfunction "2_2") (pintype "passive"))
      (node (ref "C140") (pin "2") (pinfunction "2_2") (pintype "passive"))
      (node (ref "C143") (pin "1") (pinfunction "1_1") (pintype "passive"))
      (node (ref "C144") (pin "1") (pinfunction "1_1") (pintype "passive"))
      (node (ref "C145") (pin "2") (pinfunction "2_2") (pintype "passive"))
      (node (ref "C146") (pin "2") (pinfunction "2_2") (pintype "passive"))
      (node (ref "C147") (pin "2") (pinfunction "2_2") (pintype "passive"))
      (node (ref "C149") (pin "2") (pinfunction "2_2") (pintype "passive"))
      (node (ref "J25") (pin "1") (pinfunction "sleeve_1") (pintype "passive"))
      (node (ref "J26") (pin "1") (pinfunction "sleeve_1") (pintype "passive"))
      (node (ref "J27") (pin "1") (pinfunction "sleeve_1") (pintype "passive"))
      (node (ref "J28") (pin "1") (pinfunction "sleeve_1") (pintype "passive"))
      (node (ref "R100") (pin "1") (pinfunction "1_1") (pintype "passive"))
      (node (ref "R101") (pin "1") (pinfunction "1_1") (pintype "passive"))
      (node (ref "R24") (pin "2") (pinfunction "2_2") (pintype "passive"))
      (node (ref "R90") (pin "1") (pinfunction "1_1") (pintype "passive"))
      (node (ref "R91") (pin "1") (pinfunction "1_1") (pintype "passive"))
      (node (ref "R92") (pin "1") (pinfunction "1_1") (pintype "passive"))
      (node (ref "R93") (pin "1") (pinfunction "1_1") (pintype "passive"))
      (node (ref "R96") (pin "1") (pinfunction "1_1") (pintype "passive"))
      (node (ref "R97") (pin "1") (pinfunction "1_1") (pintype "passive"))
      (node (ref "U14") (pin "1") (pinfunction "GND_1_1") (pintype "passive"))
      (node (ref "U14") (pin "3") (pinfunction "GND_2_3") (pintype "passive"))
      (node (ref "U14") (pin "31") (pinfunction "CTRL_ADR0_CS_31") (pintype "passive"))
      (node (ref "U14") (pin "32") (pinfunction "CTRL_MODE_32") (pintype "passive"))
      (node (ref "U14") (pin "33") (pinfunction "EPAD_33") (pintype "passive"))
      (node (ref "U14") (pin "7") (pinfunction "AGND_7") (pintype "passive"))
    )
    (net (code "36") (name "Net-(C120-Pad2)") (class "Default")
      (node (ref "C120") (pin "2") (pinfunction "2_2") (pintype "passive"))
      (node (ref "R92") (pin "2") (pinfunction "2_2") (pintype "passive"))
    )
    (net (code "37") (name "Net-(C121-Pad2)") (class "Default")
      (node (ref "C121") (pin "2") (pinfunction "2_2") (pintype "passive"))
      (node (ref "R93") (pin "2") (pinfunction "2_2") (pintype "passive"))
    )
    (net (code "38") (name "Net-(C130-Pad1)") (class "Default")
      (node (ref "C130") (pin "1") (pinfunction "1_1") (pintype "passive"))
      (node (ref "R94") (pin "2") (pinfunction "2_2") (pintype "passive"))
    )
    (net (code "39") (name "Net-(C130-Pad2)") (class "Default")
      (node (ref "C130") (pin "2") (pinfunction "2_2") (pintype "passive"))
      (node (ref "FB14") (pin "1") (pinfunction "1_1") (pintype "passive"))
      (node (ref "R96") (pin "2") (pinfunction "2_2") (pintype "passive"))
    )
    (net (code "40") (name "Net-(C131-Pad1)") (class "Default")
      (node (ref "C131") (pin "1") (pinfunction "1_1") (pintype "passive"))
      (node (ref "R95") (pin "2") (pinfunction "2_2") (pintype "passive"))
    )
    (net (code "41") (name "Net-(C131-Pad2)") (class "Default")
      (node (ref "C131") (pin "2") (pinfunction "2_2") (pintype "passive"))
      (node (ref "FB15") (pin "1") (pinfunction "1_1") (pintype "passive"))
      (node (ref "R97") (pin "2") (pinfunction "2_2") (pintype "passive"))
    )
    (net (code "42") (name "Net-(C141-Pad2)") (class "Default")
      (node (ref "C141") (pin "2") (pinfunction "2_2") (pintype "passive"))
      (node (ref "R100") (pin "2") (pinfunction "2_2") (pintype "passive"))
      (node (ref "R98") (pin "1") (pinfunction "1_1") (pintype "passive"))
    )
    (net (code "43") (name "Net-(C142-Pad2)") (class "Default")
      (node (ref "C142") (pin "2") (pinfunction "2_2") (pintype "passive"))
      (node (ref "R101") (pin "2") (pinfunction "2_2") (pintype "passive"))
      (node (ref "R99") (pin "1") (pinfunction "1_1") (pintype "passive"))
    )
    (net (code "44") (name "Net-(C143-Pad2)") (class "Default")
      (node (ref "C143") (pin "2") (pinfunction "2_2") (pintype "passive"))
      (node (ref "FB16") (pin "1") (pinfunction "1_1") (pintype "passive"))
      (node (ref "R98") (pin "2") (pinfunction "2_2") (pintype "passive"))
    )
    (net (code "45") (name "Net-(C144-Pad2)") (class "Default")
      (node (ref "C144") (pin "2") (pinfunction "2_2") (pintype "passive"))
      (node (ref "FB17") (pin "1") (pinfunction "1_1") (pintype "passive"))
      (node (ref "R99") (pin "2") (pinfunction "2_2") (pintype "passive"))
    )
    (net (code "46") (name "Net-(C148-Pad2)") (class "Default")
      (node (ref "C148") (pin "2") (pinfunction "2_2") (pintype "passive"))
      (node (ref "FB18") (pin "1") (pinfunction "1_1") (pintype "passive"))
      (node (ref "R102") (pin "1") (pinfunction "1_1") (pintype "passive"))
    )
    (net (code "47") (name "Net-(U14-HP_VGND)") (class "Default")
      (node (ref "R24") (pin "1") (pinfunction "1_1") (pintype "passive"))
      (node (ref "U14") (pin "4") (pinfunction "HP_VGND_4") (pintype "passive"))
    )
    (net (code "48") (name "Net-(U14-VAG)") (class "Default")
      (node (ref "C140") (pin "1") (pinfunction "1_1") (pintype "passive"))
      (node (ref "U14") (pin "10") (pinfunction "VAG_10") (pintype "passive"))
    )
    (net (code "49") (name "unconnected-(J25-ring_switch-Pad5)") (class "Default")
      (node (ref "J25") (pin "5") (pinfunction "ring_switch_5") (pintype "passive+no_connect"))
    )
    (net (code "50") (name "unconnected-(J25-tip_switch-Pad4)") (class "Default")
      (node (ref "J25") (pin "4") (pinfunction "tip_switch_4") (pintype "passive+no_connect"))
    )
    (net (code "51") (name "unconnected-(J26-ring_switch-Pad5)") (class "Default")
      (node (ref "J26") (pin "5") (pinfunction "ring_switch_5") (pintype "passive+no_connect"))
    )
    (net (code "52") (name "unconnected-(J26-tip_switch-Pad4)") (class "Default")
      (node (ref "J26") (pin "4") (pinfunction "tip_switch_4") (pintype "passive+no_connect"))
    )
    (net (code "53") (name "unconnected-(J27-ring_switch-Pad5)") (class "Default")
      (node (ref "J27") (pin "5") (pinfunction "ring_switch_5") (pintype "passive+no_connect"))
    )
    (net (code "54") (name "unconnected-(J27-tip_switch-Pad4)") (class "Default")
      (node (ref "J27") (pin "4") (pinfunction "tip_switch_4") (pintype "passive+no_connect"))
    )
    (net (code "55") (name "unconnected-(J28-ring_switch-Pad5)") (class "Default")
      (node (ref "J28") (pin "5") (pinfunction "ring_switch_5") (pintype "passive+no_connect"))
    )
    (net (code "56") (name "unconnected-(J28-tip_switch-Pad4)") (class "Default")
      (node (ref "J28") (pin "4") (pinfunction "tip_switch_4") (pintype "passive+no_connect"))
    )
    (net (code "57") (name "unconnected-(U14-CPFILT-Pad18)") (class "Default")
      (node (ref "U14") (pin "18") (pinfunction "CPFILT_18") (pintype "passive+no_connect"))
    )
    (net (code "58") (name "unconnected-(U14-NC_1-Pad8)") (class "Default")
      (node (ref "U14") (pin "8") (pinfunction "NC_1_8") (pintype "passive+no_connect"))
    )
    (net (code "59") (name "unconnected-(U14-NC_2-Pad9)") (class "Default")
      (node (ref "U14") (pin "9") (pinfunction "NC_2_9") (pintype "passive+no_connect"))
    )
    (net (code "60") (name "unconnected-(U14-NC_3-Pad17)") (class "Default")
      (node (ref "U14") (pin "17") (pinfunction "NC_3_17") (pintype "passive+no_connect"))
    )
    (net (code "61") (name "unconnected-(U14-NC_4-Pad19)") (class "Default")
      (node (ref "U14") (pin "19") (pinfunction "NC_4_19") (pintype "passive+no_connect"))
    )
    (net (code "62") (name "unconnected-(U14-NC_5-Pad22)") (class "Default")
      (node (ref "U14") (pin "22") (pinfunction "NC_5_22") (pintype "passive+no_connect"))
    )
    (net (code "63") (name "unconnected-(U14-NC_6-Pad28)") (class "Default")
      (node (ref "U14") (pin "28") (pinfunction "NC_6_28") (pintype "passive+no_connect"))
    )
  )
)
